# 01-Antennas.net
KiCad netlist of a schematic drawn in Altium Designer
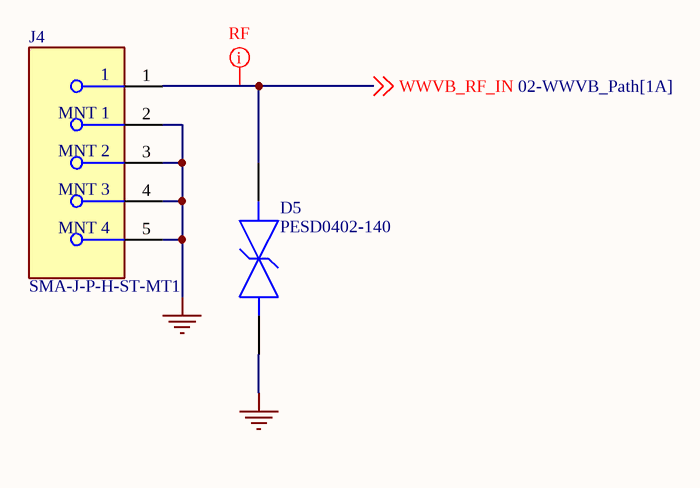
[diagram p0: 01-Antennas.SchDoc]

(export (version "E")
  (design (tool "Eeschema 10.0.6"))
  (components
    (comp (ref "D5")
      (value "PESD0402-140")
      (footprint "FP-PESD0402-MFG")
      (description "TVS DIODE 14V 40V 0402")
      (fields
        (field (name "OCTOPART") "https://octopart.com/pesd0402-140-littelfuse-74215061")
        (field (name "MANUFACTURER") "Littelfuse Inc.")
      )
      (libsource (lib "Altium Content Vault") (part "edccc070dd5cba1f9372128faf3915e"))
    )
    (comp (ref "J4")
      (value "SMA-J-P-H-ST-MT1")
      (footprint "FP-SMA-J-P-H-ST-MT1-MFG")
      (description "CONN SMA JACK STR 50 OHM SMD")
      (libsource (lib "Altium Content Vault") (part "9c40ac4d87bbbe9fcb330bd20f98ca3"))
    )
  )
  (nets
    (net (code "1") (name "GND") (class "Default")
      (node (ref "D5") (pin "1") (pinfunction "1_1") (pintype "passive"))
      (node (ref "J4") (pin "2") (pinfunction "MNT_1_2") (pintype "passive"))
      (node (ref "J4") (pin "3") (pinfunction "MNT_2_3") (pintype "passive"))
      (node (ref "J4") (pin "4") (pinfunction "MNT_3_4") (pintype "passive"))
      (node (ref "J4") (pin "5") (pinfunction "MNT_4_5") (pintype "passive"))
    )
    (net (code "2") (name "WWVB_RF_IN") (class "Default")
      (node (ref "D5") (pin "2") (pinfunction "2_2") (pintype "passive"))
      (node (ref "J4") (pin "1") (pinfunction "1_1") (pintype "passive"))
    )
  )
)
